# Interfaces_and_Connectors.net
KiCad netlist of a schematic drawn in Altium Designer
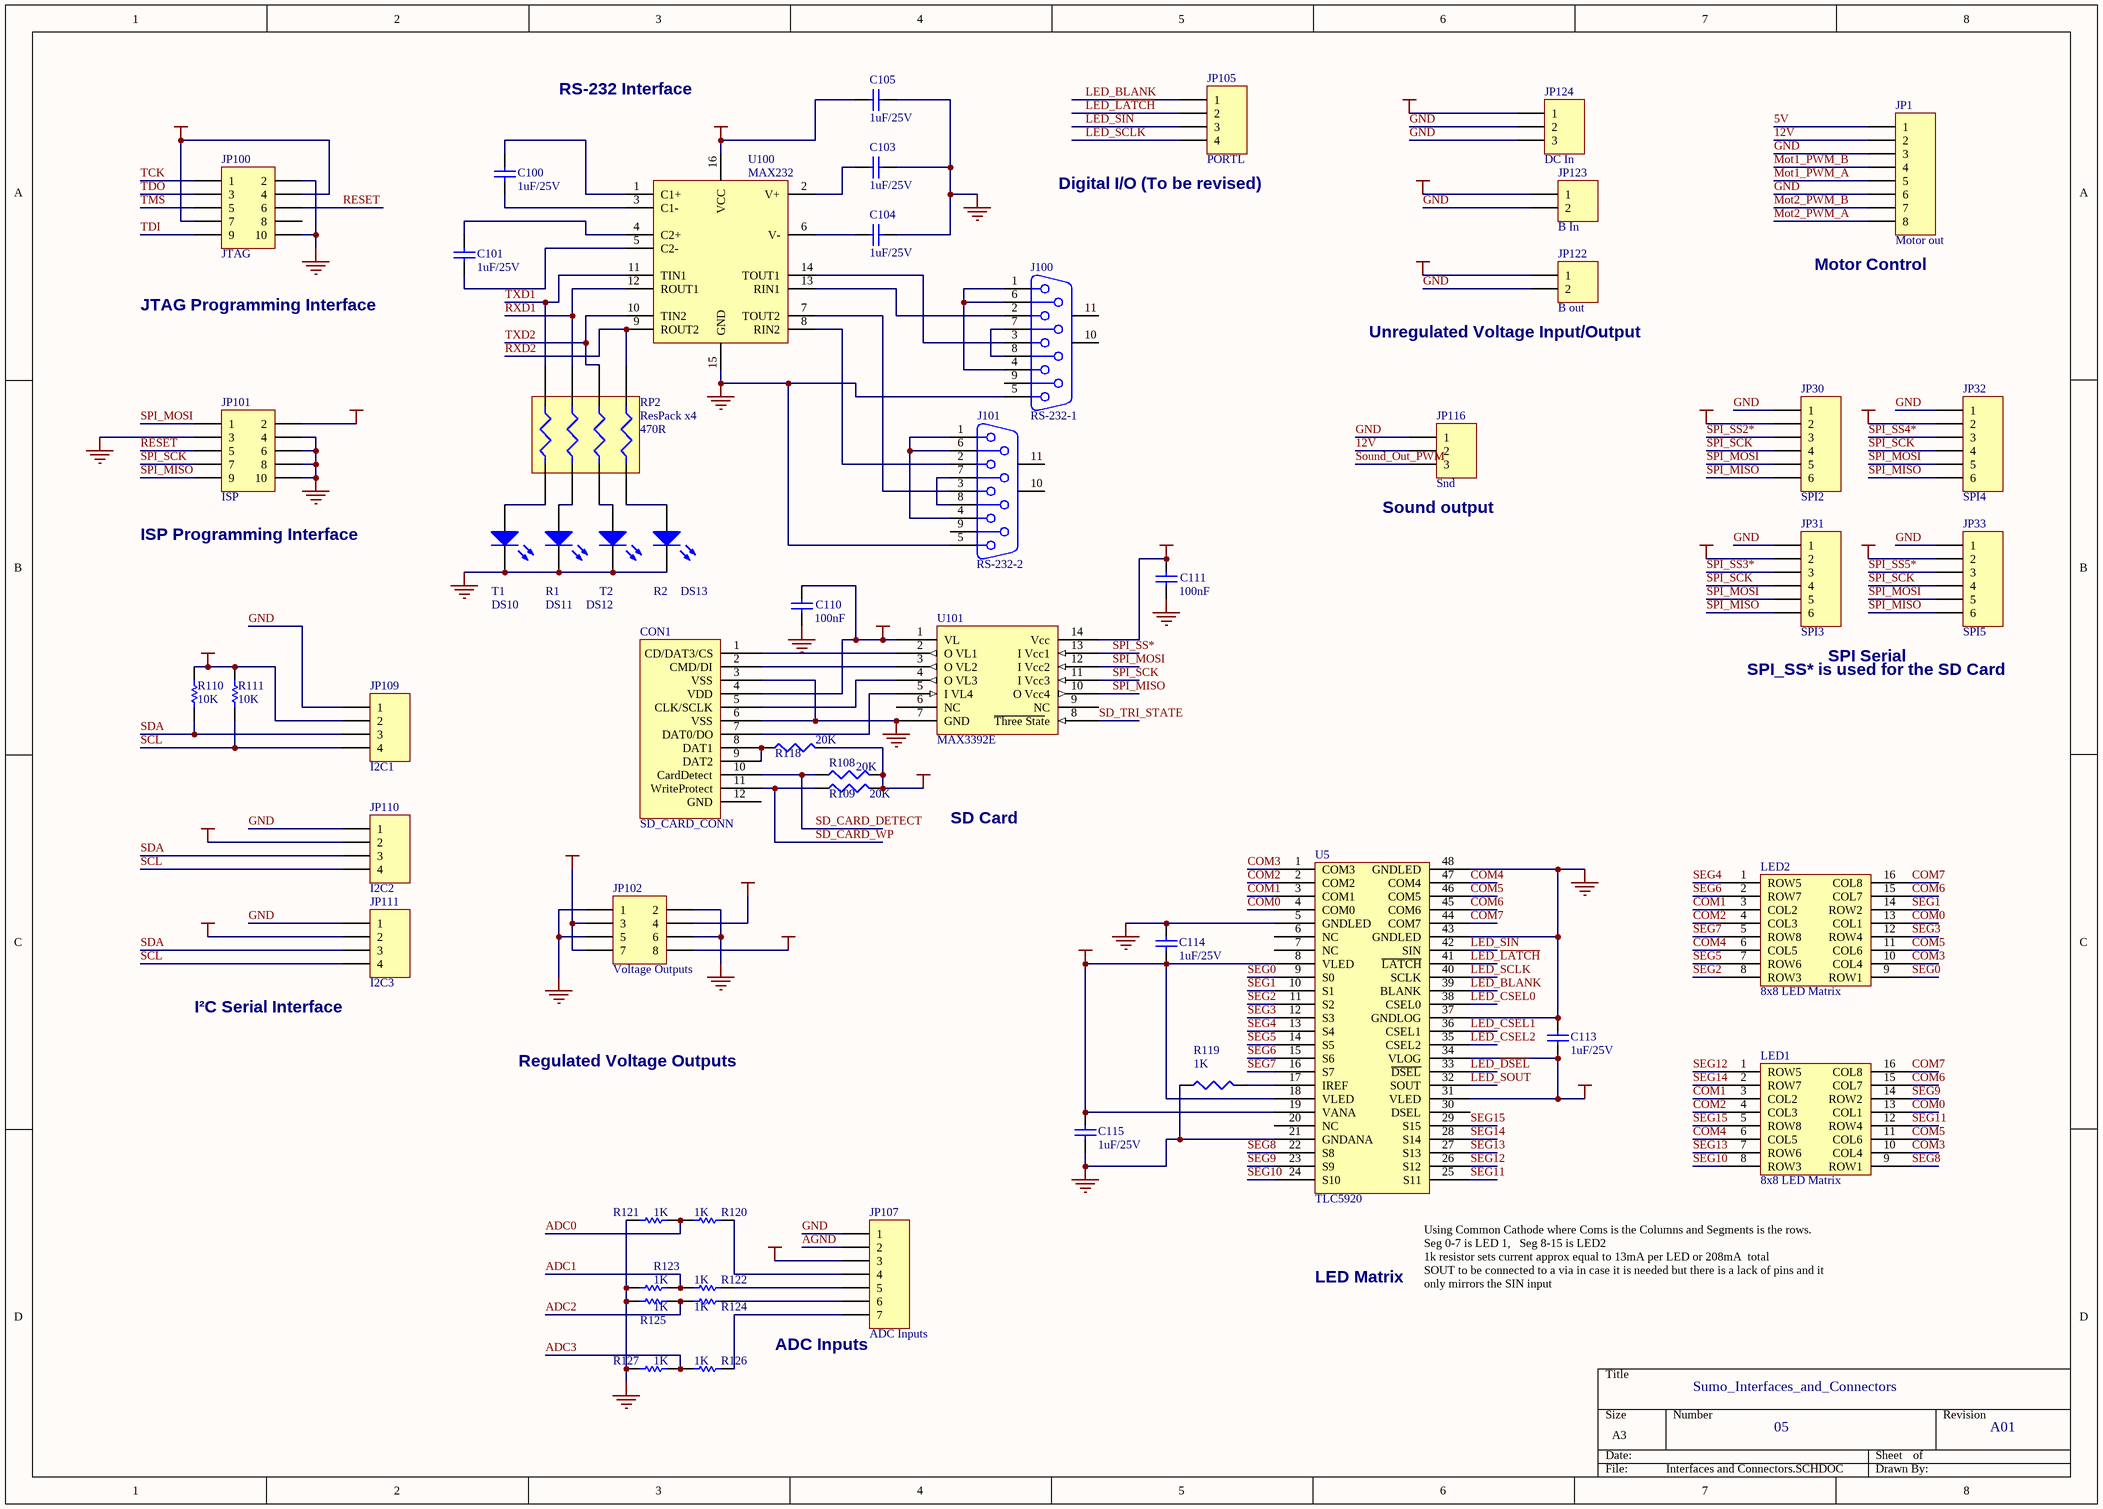
[diagram p0: Interfaces and Connectors.SCHDOC]

(export (version "E")
  (design (tool "Eeschema 10.0.6"))
  (components
    (comp (ref "C100")
      (value "1uF/25V")
      (footprint "CC2012-0805")
      (description "Capacitor (Semiconductor SIM Model)")
      (fields (field (name "Comment") "Cap Semi") (field (name "PUBLISHER") "Altium Limited"))
      (libsource (lib "Miscellaneous Devices") (part "Cap Semi"))
    )
    (comp (ref "C101")
      (value "1uF/25V")
      (footprint "CC2012-0805")
      (description "Capacitor (Semiconductor SIM Model)")
      (fields (field (name "Comment") "Cap Semi") (field (name "PUBLISHER") "Altium Limited"))
      (libsource (lib "Miscellaneous Devices") (part "Cap Semi"))
    )
    (comp (ref "C103")
      (value "1uF/25V")
      (footprint "CC2012-0805")
      (description "Capacitor (Semiconductor SIM Model)")
      (fields (field (name "Comment") "Cap Semi") (field (name "PUBLISHER") "Altium Limited"))
      (libsource (lib "Miscellaneous Devices") (part "Cap Semi"))
    )
    (comp (ref "C104")
      (value "1uF/25V")
      (footprint "CC2012-0805")
      (description "Capacitor (Semiconductor SIM Model)")
      (fields (field (name "Comment") "Cap Semi") (field (name "PUBLISHER") "Altium Limited"))
      (libsource (lib "Miscellaneous Devices") (part "Cap Semi"))
    )
    (comp (ref "C105")
      (value "1uF/25V")
      (footprint "CC2012-0805")
      (description "Capacitor (Semiconductor SIM Model)")
      (fields (field (name "Comment") "Cap Semi") (field (name "PUBLISHER") "Altium Limited"))
      (libsource (lib "Miscellaneous Devices") (part "Cap Semi"))
    )
    (comp (ref "C110")
      (value "100nF")
      (footprint "CC2012-0805")
      (description "Capacitor (Semiconductor SIM Model)")
      (fields (field (name "Comment") "Cap Semi") (field (name "PUBLISHER") "Altium Limited"))
      (libsource (lib "Miscellaneous Devices") (part "Cap Semi"))
    )
    (comp (ref "C111")
      (value "100nF")
      (footprint "CC2012-0805")
      (description "Capacitor (Semiconductor SIM Model)")
      (fields (field (name "Comment") "Cap Semi") (field (name "PUBLISHER") "Altium Limited"))
      (libsource (lib "Miscellaneous Devices") (part "Cap Semi"))
    )
    (comp (ref "C113")
      (value "1uF/25V")
      (footprint "CC2012-0805")
      (description "Capacitor (Semiconductor SIM Model)")
      (fields (field (name "Comment") "Cap Semi") (field (name "PUBLISHER") "Altium Limited"))
      (libsource (lib "Miscellaneous Devices") (part "Cap Semi"))
    )
    (comp (ref "C114")
      (value "1uF/25V")
      (footprint "CC2012-0805")
      (description "Capacitor (Semiconductor SIM Model)")
      (fields (field (name "Comment") "Cap Semi") (field (name "PUBLISHER") "Altium Limited"))
      (libsource (lib "Miscellaneous Devices") (part "Cap Semi"))
    )
    (comp (ref "C115")
      (value "1uF/25V")
      (footprint "CC2012-0805")
      (description "Capacitor (Semiconductor SIM Model)")
      (fields (field (name "Comment") "Cap Semi") (field (name "PUBLISHER") "Altium Limited"))
      (libsource (lib "Miscellaneous Devices") (part "Cap Semi"))
    )
    (comp (ref "CON1")
      (value "SD_CARD_CONN")
      (footprint "SD Card AVX")
      (libsource (lib "Sumo") (part "SD_CARD_CONN"))
    )
    (comp (ref "DS10")
      (value "T1")
      (footprint "SMD _LED")
      (description "Typical BLUE SiC LED")
      (fields (field (name "PUBLISHER") "Altium Limited"))
      (libsource (lib "Miscellaneous Devices") (part "LED3"))
    )
    (comp (ref "DS11")
      (value "R1")
      (footprint "SMD _LED")
      (description "Typical BLUE SiC LED")
      (fields (field (name "PUBLISHER") "Altium Limited"))
      (libsource (lib "Miscellaneous Devices") (part "LED3"))
    )
    (comp (ref "DS12")
      (value "T2")
      (footprint "SMD _LED")
      (description "Typical BLUE SiC LED")
      (fields (field (name "PUBLISHER") "Altium Limited"))
      (libsource (lib "Miscellaneous Devices") (part "LED3"))
    )
    (comp (ref "DS13")
      (value "R2")
      (footprint "SMD _LED")
      (description "Typical BLUE SiC LED")
      (fields (field (name "PUBLISHER") "Altium Limited"))
      (libsource (lib "Miscellaneous Devices") (part "LED3"))
    )
    (comp (ref "J100")
      (value "RS-232-1")
      (footprint "DSUB1.385-2H9 Simple")
      (description "Receptacle Assembly, 9 Position, Right Angle")
      (fields (field (name "PUBLISHER") "Altium Limited"))
      (libsource (lib "Miscellaneous Connectors") (part "D Connector 9"))
    )
    (comp (ref "J101")
      (value "RS-232-2")
      (footprint "DSUB1.385-2H9 Simple")
      (description "Receptacle Assembly, 9 Position, Right Angle")
      (fields (field (name "PUBLISHER") "Altium Limited"))
      (libsource (lib "Miscellaneous Connectors") (part "D Connector 9"))
    )
    (comp (ref "JP1")
      (value "Motor out")
      (footprint "PHR 1x8 2mm")
      (description "Header, 8-Pin")
      (fields (field (name "PUBLISHER") "Altium Limited"))
      (libsource (lib "Miscellaneous Connectors") (part "Header 8"))
    )
    (comp (ref "JP30")
      (value "SPI2")
      (footprint "ZHR 1x6 1.5mm")
      (description "Header, 6-Pin")
      (fields (field (name "PUBLISHER") "Altium Limited"))
      (libsource (lib "Miscellaneous Connectors") (part "Header 6"))
    )
    (comp (ref "JP31")
      (value "SPI3")
      (footprint "ZHR 1x6 1.5mm")
      (description "Header, 6-Pin")
      (fields (field (name "PUBLISHER") "Altium Limited"))
      (libsource (lib "Miscellaneous Connectors") (part "Header 6"))
    )
    (comp (ref "JP32")
      (value "SPI4")
      (footprint "ZHR 1x6 1.5mm")
      (description "Header, 6-Pin")
      (fields (field (name "PUBLISHER") "Altium Limited"))
      (libsource (lib "Miscellaneous Connectors") (part "Header 6"))
    )
    (comp (ref "JP33")
      (value "SPI5")
      (footprint "ZHR 1x6 1.5mm")
      (description "Header, 6-Pin")
      (fields (field (name "PUBLISHER") "Altium Limited"))
      (libsource (lib "Miscellaneous Connectors") (part "Header 6"))
    )
    (comp (ref "JP100")
      (value "JTAG")
      (footprint "HDR2X5")
      (description "Header, 5-Pin, Dual row")
      (fields (field (name "PUBLISHER") "Altium Limited"))
      (libsource (lib "Miscellaneous Connectors") (part "Header 5X2"))
    )
    (comp (ref "JP101")
      (value "ISP")
      (footprint "HDR2X5")
      (description "Header, 5-Pin, Dual row")
      (fields (field (name "PUBLISHER") "Altium Limited"))
      (libsource (lib "Miscellaneous Connectors") (part "Header 5X2"))
    )
    (comp (ref "JP102")
      (value "Voltage Outputs")
      (footprint "microfit 2x4 3mm")
      (description "Header, 4-Pin, Dual row")
      (fields (field (name "PUBLISHER") "Altium Limited"))
      (libsource (lib "Miscellaneous Connectors") (part "Header 4X2"))
    )
    (comp (ref "JP105")
      (value "PORTL")
      (footprint "EHR 1x4 2.5mm")
      (description "Header, 4-Pin")
      (fields (field (name "PUBLISHER") "Altium Limited"))
      (libsource (lib "Miscellaneous Connectors") (part "Header 4"))
    )
    (comp (ref "JP107")
      (value "ADC Inputs")
      (footprint "KK 1x7 2.54mm")
      (description "Header, 7-Pin")
      (fields (field (name "PUBLISHER") "Altium Limited"))
      (libsource (lib "Miscellaneous Connectors") (part "Header 7"))
    )
    (comp (ref "JP109")
      (value "I2C1")
      (footprint "ZHR 1x4 1.5mm")
      (description "Header, 4-Pin")
      (fields (field (name "PUBLISHER") "Altium Limited"))
      (libsource (lib "Miscellaneous Connectors") (part "Header 4"))
    )
    (comp (ref "JP110")
      (value "I2C2")
      (footprint "ZHR 1x4 1.5mm")
      (description "Header, 4-Pin")
      (fields (field (name "PUBLISHER") "Altium Limited"))
      (libsource (lib "Miscellaneous Connectors") (part "Header 4"))
    )
    (comp (ref "JP111")
      (value "I2C3")
      (footprint "ZHR 1x4 1.5mm")
      (description "Header, 4-Pin")
      (fields (field (name "PUBLISHER") "Altium Limited"))
      (libsource (lib "Miscellaneous Connectors") (part "Header 4"))
    )
    (comp (ref "JP116")
      (value "Snd")
      (footprint "KK 1x3 2.54mm")
      (description "Header, 3-Pin")
      (fields (field (name "PUBLISHER") "Altium Limited"))
      (libsource (lib "Miscellaneous Connectors") (part "Header 3"))
    )
    (comp (ref "JP122")
      (value "B out")
      (footprint "Mini-Fit Jnr 2x1 4.2mm")
      (description "Header, 2-Pin")
      (fields (field (name "PUBLISHER") "Altium Limited"))
      (libsource (lib "Miscellaneous Connectors") (part "Header 2"))
    )
    (comp (ref "JP123")
      (value "B In")
      (footprint "Mini-Fit Jnr 2x1 4.2mm")
      (description "Header, 2-Pin")
      (fields (field (name "PUBLISHER") "Altium Limited"))
      (libsource (lib "Miscellaneous Connectors") (part "Header 2"))
    )
    (comp (ref "JP124")
      (value "DC In")
      (footprint "DC Jack 2.1mm")
      (description "Header, 3-Pin")
      (fields (field (name "PUBLISHER") "Altium Limited"))
      (libsource (lib "Miscellaneous Connectors") (part "Header 3"))
    )
    (comp (ref "LED1")
      (value "8x8 LED Matrix")
      (footprint "8x8 LED matrix")
      (libsource (lib "Sumo") (part "8x8 LED Matrix"))
    )
    (comp (ref "LED2")
      (value "8x8 LED Matrix")
      (footprint "8x8 LED matrix")
      (libsource (lib "Sumo") (part "8x8 LED Matrix"))
    )
    (comp (ref "R108")
      (value "20K")
      (footprint "CR2012-0805")
      (description "Resistor")
      (fields (field (name "Comment") "Res3") (field (name "PUBLISHER") "Altium Limited"))
      (libsource (lib "Miscellaneous Devices") (part "Res3"))
    )
    (comp (ref "R109")
      (value "20K")
      (footprint "CR2012-0805")
      (description "Resistor")
      (fields (field (name "Comment") "Res3") (field (name "PUBLISHER") "Altium Limited"))
      (libsource (lib "Miscellaneous Devices") (part "Res3"))
    )
    (comp (ref "R110")
      (value "10K")
      (footprint "CR2012-0805")
      (description "Resistor")
      (fields (field (name "PUBLISHER") "Altium Limited"))
      (libsource (lib "Miscellaneous Devices") (part "Res1"))
    )
    (comp (ref "R111")
      (value "10K")
      (footprint "CR2012-0805")
      (description "Resistor")
      (fields (field (name "PUBLISHER") "Altium Limited"))
      (libsource (lib "Miscellaneous Devices") (part "Res1"))
    )
    (comp (ref "R118")
      (value "20K")
      (footprint "CR2012-0805")
      (description "Resistor")
      (fields (field (name "Comment") "Res3") (field (name "PUBLISHER") "Altium Limited"))
      (libsource (lib "Miscellaneous Devices") (part "Res3"))
    )
    (comp (ref "R119")
      (value "1K")
      (footprint "CR2012-0805")
      (description "Resistor")
      (fields (field (name "Comment") "Res3") (field (name "PUBLISHER") "Altium Limited"))
      (libsource (lib "Miscellaneous Devices") (part "Res3"))
    )
    (comp (ref "R120")
      (value "1K")
      (footprint "CR2012-0805")
      (description "Resistor")
      (fields (field (name "Comment") "Res1") (field (name "PUBLISHER") "Altium Limited"))
      (libsource (lib "Miscellaneous Devices") (part "Res1"))
    )
    (comp (ref "R121")
      (value "1K")
      (footprint "CR2012-0805")
      (description "Resistor")
      (fields (field (name "Comment") "Res1") (field (name "PUBLISHER") "Altium Limited"))
      (libsource (lib "Miscellaneous Devices") (part "Res1"))
    )
    (comp (ref "R122")
      (value "1K")
      (footprint "CR2012-0805")
      (description "Resistor")
      (fields (field (name "Comment") "Res1") (field (name "PUBLISHER") "Altium Limited"))
      (libsource (lib "Miscellaneous Devices") (part "Res1"))
    )
    (comp (ref "R123")
      (value "1K")
      (footprint "CR2012-0805")
      (description "Resistor")
      (fields (field (name "Comment") "Res1") (field (name "PUBLISHER") "Altium Limited"))
      (libsource (lib "Miscellaneous Devices") (part "Res1"))
    )
    (comp (ref "R124")
      (value "1K")
      (footprint "CR2012-0805")
      (description "Resistor")
      (fields (field (name "Comment") "Res1") (field (name "PUBLISHER") "Altium Limited"))
      (libsource (lib "Miscellaneous Devices") (part "Res1"))
    )
    (comp (ref "R125")
      (value "1K")
      (footprint "CR2012-0805")
      (description "Resistor")
      (fields (field (name "Comment") "Res1") (field (name "PUBLISHER") "Altium Limited"))
      (libsource (lib "Miscellaneous Devices") (part "Res1"))
    )
    (comp (ref "R126")
      (value "1K")
      (footprint "CR2012-0805")
      (description "Resistor")
      (fields (field (name "Comment") "Res1") (field (name "PUBLISHER") "Altium Limited"))
      (libsource (lib "Miscellaneous Devices") (part "Res1"))
    )
    (comp (ref "R127")
      (value "1K")
      (footprint "CR2012-0805")
      (description "Resistor")
      (fields (field (name "Comment") "Res1") (field (name "PUBLISHER") "Altium Limited"))
      (libsource (lib "Miscellaneous Devices") (part "Res1"))
    )
    (comp (ref "RP2")
      (value "ResPack x4")
      (footprint "4x0603 Resistor pack")
      (fields (field (name "ALTIUM_VALUE") "470R"))
      (libsource (lib "Sumo") (part "ResPack x4"))
    )
    (comp (ref "U5")
      (value "TLC5920")
      (footprint "SSO-G48")
      (description "TLC5920 16x8 LED Driver")
      (libsource (lib "Sumo") (part "TLC5920 16x8 LED Driver"))
    )
    (comp (ref "U100")
      (value "MAX232")
      (footprint "SO-G16/C5.85")
      (description "Maxim RS-232 Transceiver")
      (libsource (lib "Sumo") (part "MAX232"))
    )
    (comp (ref "U101") (value "MAX3392E") (footprint "TSSOP14") (libsource (lib "Sumo") (part "MAX3392E")))
  )
  (nets
    (net (code "1") (name "/ADC0") (class "Default")
      (node (ref "R120") (pin "1") (pinfunction "1_1") (pintype "passive"))
      (node (ref "R121") (pin "2") (pinfunction "2_2") (pintype "passive"))
    )
    (net (code "2") (name "/ADC1") (class "Default")
      (node (ref "R122") (pin "1") (pinfunction "1_1") (pintype "passive"))
      (node (ref "R123") (pin "2") (pinfunction "2_2") (pintype "passive"))
    )
    (net (code "3") (name "/ADC2") (class "Default")
      (node (ref "R124") (pin "1") (pinfunction "1_1") (pintype "passive"))
      (node (ref "R125") (pin "2") (pinfunction "2_2") (pintype "passive"))
    )
    (net (code "4") (name "/ADC3") (class "Default")
      (node (ref "R126") (pin "1") (pinfunction "1_1") (pintype "passive"))
      (node (ref "R127") (pin "2") (pinfunction "2_2") (pintype "passive"))
    )
    (net (code "5") (name "/COM0") (class "Default")
      (node (ref "LED1") (pin "13") (pinfunction "COL1_13") (pintype "passive"))
      (node (ref "LED2") (pin "13") (pinfunction "COL1_13") (pintype "passive"))
      (node (ref "U5") (pin "4") (pinfunction "COM0_4") (pintype "passive"))
    )
    (net (code "6") (name "/COM1") (class "Default")
      (node (ref "LED1") (pin "3") (pinfunction "COL2_3") (pintype "passive"))
      (node (ref "LED2") (pin "3") (pinfunction "COL2_3") (pintype "passive"))
      (node (ref "U5") (pin "3") (pinfunction "COM1_3") (pintype "passive"))
    )
    (net (code "7") (name "/COM2") (class "Default")
      (node (ref "LED1") (pin "4") (pinfunction "COL3_4") (pintype "passive"))
      (node (ref "LED2") (pin "4") (pinfunction "COL3_4") (pintype "passive"))
      (node (ref "U5") (pin "2") (pinfunction "COM2_2") (pintype "passive"))
    )
    (net (code "8") (name "/COM3") (class "Default")
      (node (ref "LED1") (pin "10") (pinfunction "COL4_10") (pintype "passive"))
      (node (ref "LED2") (pin "10") (pinfunction "COL4_10") (pintype "passive"))
      (node (ref "U5") (pin "1") (pinfunction "COM3_1") (pintype "passive"))
    )
    (net (code "9") (name "/COM4") (class "Default")
      (node (ref "LED1") (pin "6") (pinfunction "COL5_6") (pintype "passive"))
      (node (ref "LED2") (pin "6") (pinfunction "COL5_6") (pintype "passive"))
      (node (ref "U5") (pin "47") (pinfunction "COM4_47") (pintype "passive"))
    )
    (net (code "10") (name "/COM5") (class "Default")
      (node (ref "LED1") (pin "11") (pinfunction "COL6_11") (pintype "passive"))
      (node (ref "LED2") (pin "11") (pinfunction "COL6_11") (pintype "passive"))
      (node (ref "U5") (pin "46") (pinfunction "COM5_46") (pintype "passive"))
    )
    (net (code "11") (name "/COM6") (class "Default")
      (node (ref "LED1") (pin "15") (pinfunction "COL7_15") (pintype "passive"))
      (node (ref "LED2") (pin "15") (pinfunction "COL7_15") (pintype "passive"))
      (node (ref "U5") (pin "45") (pinfunction "COM6_45") (pintype "passive"))
    )
    (net (code "12") (name "/COM7") (class "Default")
      (node (ref "LED1") (pin "16") (pinfunction "COL8_16") (pintype "passive"))
      (node (ref "LED2") (pin "16") (pinfunction "COL8_16") (pintype "passive"))
      (node (ref "U5") (pin "44") (pinfunction "COM7_44") (pintype "passive"))
    )
    (net (code "13") (name "/LED_BLANK") (class "Default")
      (node (ref "JP105") (pin "1") (pinfunction "1_1") (pintype "passive"))
      (node (ref "U5") (pin "39") (pinfunction "BLANK_39") (pintype "passive"))
    )
    (net (code "14") (name "/LED_CSEL0") (class "Default")
      (node (ref "U5") (pin "38") (pinfunction "CSEL0_38") (pintype "passive"))
    )
    (net (code "15") (name "/LED_CSEL1") (class "Default")
      (node (ref "U5") (pin "36") (pinfunction "CSEL1_36") (pintype "passive"))
    )
    (net (code "16") (name "/LED_CSEL2") (class "Default")
      (node (ref "U5") (pin "35") (pinfunction "CSEL2_35") (pintype "passive"))
    )
    (net (code "17") (name "/LED_SCLK") (class "Default")
      (node (ref "JP105") (pin "4") (pinfunction "4_4") (pintype "passive"))
      (node (ref "U5") (pin "40") (pinfunction "SCLK_40") (pintype "passive"))
    )
    (net (code "18") (name "/LED_SIN") (class "Default")
      (node (ref "JP105") (pin "3") (pinfunction "3_3") (pintype "passive"))
      (node (ref "U5") (pin "42") (pinfunction "SIN_42") (pintype "passive"))
    )
    (net (code "19") (name "/LED_SOUT") (class "Default")
      (node (ref "U5") (pin "32") (pinfunction "SOUT_32") (pintype "passive"))
    )
    (net (code "20") (name "/LED_~{DSEL}") (class "Default")
      (node (ref "U5") (pin "33") (pinfunction "~{DSEL}_33") (pintype "passive"))
    )
    (net (code "21") (name "/LED_~{LATCH}") (class "Default")
      (node (ref "JP105") (pin "2") (pinfunction "2_2") (pintype "passive"))
      (node (ref "U5") (pin "41") (pinfunction "~{LATCH}_41") (pintype "passive"))
    )
    (net (code "22") (name "/Mot1_PWM_A") (class "Default")
      (node (ref "JP1") (pin "5") (pinfunction "5_5") (pintype "passive"))
    )
    (net (code "23") (name "/Mot1_PWM_B") (class "Default")
      (node (ref "JP1") (pin "4") (pinfunction "4_4") (pintype "passive"))
    )
    (net (code "24") (name "/Mot2_PWM_A") (class "Default")
      (node (ref "JP1") (pin "8") (pinfunction "8_8") (pintype "passive"))
    )
    (net (code "25") (name "/Mot2_PWM_B") (class "Default")
      (node (ref "JP1") (pin "7") (pinfunction "7_7") (pintype "passive"))
    )
    (net (code "26") (name "/RESET") (class "Default")
      (node (ref "JP100") (pin "6") (pinfunction "6_6") (pintype "passive"))
      (node (ref "JP101") (pin "5") (pinfunction "5_5") (pintype "passive"))
    )
    (net (code "27") (name "/RXD1") (class "Default")
      (node (ref "RP2") (pin "7") (pintype "passive"))
      (node (ref "U100") (pin "12") (pinfunction "ROUT1_12") (pintype "passive"))
    )
    (net (code "28") (name "/RXD2") (class "Default")
      (node (ref "RP2") (pin "5") (pintype "passive"))
      (node (ref "U100") (pin "9") (pinfunction "ROUT2_9") (pintype "passive"))
    )
    (net (code "29") (name "/SCL") (class "Default")
      (node (ref "JP109") (pin "4") (pinfunction "4_4") (pintype "passive"))
      (node (ref "JP110") (pin "4") (pinfunction "4_4") (pintype "passive"))
      (node (ref "JP111") (pin "4") (pinfunction "4_4") (pintype "passive"))
      (node (ref "R111") (pin "1") (pinfunction "1_1") (pintype "passive"))
    )
    (net (code "30") (name "/SDA") (class "Default")
      (node (ref "JP109") (pin "3") (pinfunction "3_3") (pintype "passive"))
      (node (ref "JP110") (pin "3") (pinfunction "3_3") (pintype "passive"))
      (node (ref "JP111") (pin "3") (pinfunction "3_3") (pintype "passive"))
      (node (ref "R110") (pin "1") (pinfunction "1_1") (pintype "passive"))
    )
    (net (code "31") (name "/SD_CARD_DETECT") (class "Default")
      (node (ref "CON1") (pin "10") (pinfunction "CardDetect_10") (pintype "passive"))
      (node (ref "R108") (pin "1") (pinfunction "1_1") (pintype "passive"))
    )
    (net (code "32") (name "/SD_CARD_WP") (class "Default")
      (node (ref "CON1") (pin "11") (pinfunction "WriteProtect_11") (pintype "passive"))
      (node (ref "R109") (pin "1") (pinfunction "1_1") (pintype "passive"))
    )
    (net (code "33") (name "/SD_TRI_STATE") (class "Default")
      (node (ref "U101") (pin "8") (pinfunction "~{Three_Stat}e_8") (pintype "input"))
    )
    (net (code "34") (name "/SEG0") (class "Default")
      (node (ref "LED2") (pin "9") (pinfunction "ROW1_9") (pintype "passive"))
      (node (ref "U5") (pin "9") (pinfunction "S0_9") (pintype "passive"))
    )
    (net (code "35") (name "/SEG1") (class "Default")
      (node (ref "LED2") (pin "14") (pinfunction "ROW2_14") (pintype "passive"))
      (node (ref "U5") (pin "10") (pinfunction "S1_10") (pintype "passive"))
    )
    (net (code "36") (name "/SEG2") (class "Default")
      (node (ref "LED2") (pin "8") (pinfunction "ROW3_8") (pintype "passive"))
      (node (ref "U5") (pin "11") (pinfunction "S2_11") (pintype "passive"))
    )
    (net (code "37") (name "/SEG3") (class "Default")
      (node (ref "LED2") (pin "12") (pinfunction "ROW4_12") (pintype "passive"))
      (node (ref "U5") (pin "12") (pinfunction "S3_12") (pintype "passive"))
    )
    (net (code "38") (name "/SEG4") (class "Default")
      (node (ref "LED2") (pin "1") (pinfunction "ROW5_1") (pintype "passive"))
      (node (ref "U5") (pin "13") (pinfunction "S4_13") (pintype "passive"))
    )
    (net (code "39") (name "/SEG5") (class "Default")
      (node (ref "LED2") (pin "7") (pinfunction "ROW6_7") (pintype "passive"))
      (node (ref "U5") (pin "14") (pinfunction "S5_14") (pintype "passive"))
    )
    (net (code "40") (name "/SEG6") (class "Default")
      (node (ref "LED2") (pin "2") (pinfunction "ROW7_2") (pintype "passive"))
      (node (ref "U5") (pin "15") (pinfunction "S6_15") (pintype "passive"))
    )
    (net (code "41") (name "/SEG7") (class "Default")
      (node (ref "LED2") (pin "5") (pinfunction "ROW8_5") (pintype "passive"))
      (node (ref "U5") (pin "16") (pinfunction "S7_16") (pintype "passive"))
    )
    (net (code "42") (name "/SEG8") (class "Default")
      (node (ref "LED1") (pin "9") (pinfunction "ROW1_9") (pintype "passive"))
      (node (ref "U5") (pin "22") (pinfunction "S8_22") (pintype "passive"))
    )
    (net (code "43") (name "/SEG9") (class "Default")
      (node (ref "LED1") (pin "14") (pinfunction "ROW2_14") (pintype "passive"))
      (node (ref "U5") (pin "23") (pinfunction "S9_23") (pintype "passive"))
    )
    (net (code "44") (name "/SEG10") (class "Default")
      (node (ref "LED1") (pin "8") (pinfunction "ROW3_8") (pintype "passive"))
      (node (ref "U5") (pin "24") (pinfunction "S10_24") (pintype "passive"))
    )
    (net (code "45") (name "/SEG11") (class "Default")
      (node (ref "LED1") (pin "12") (pinfunction "ROW4_12") (pintype "passive"))
      (node (ref "U5") (pin "25") (pinfunction "S11_25") (pintype "passive"))
    )
    (net (code "46") (name "/SEG12") (class "Default")
      (node (ref "LED1") (pin "1") (pinfunction "ROW5_1") (pintype "passive"))
      (node (ref "U5") (pin "26") (pinfunction "S12_26") (pintype "passive"))
    )
    (net (code "47") (name "/SEG13") (class "Default")
      (node (ref "LED1") (pin "7") (pinfunction "ROW6_7") (pintype "passive"))
      (node (ref "U5") (pin "27") (pinfunction "S13_27") (pintype "passive"))
    )
    (net (code "48") (name "/SEG14") (class "Default")
      (node (ref "LED1") (pin "2") (pinfunction "ROW7_2") (pintype "passive"))
      (node (ref "U5") (pin "28") (pinfunction "S14_28") (pintype "passive"))
    )
    (net (code "49") (name "/SEG15") (class "Default")
      (node (ref "LED1") (pin "5") (pinfunction "ROW8_5") (pintype "passive"))
      (node (ref "U5") (pin "29") (pinfunction "S15_29") (pintype "passive"))
    )
    (net (code "50") (name "/SPI_MISO") (class "Default")
      (node (ref "JP101") (pin "9") (pinfunction "9_9") (pintype "passive"))
      (node (ref "JP30") (pin "6") (pinfunction "6_6") (pintype "passive"))
      (node (ref "JP31") (pin "6") (pinfunction "6_6") (pintype "passive"))
      (node (ref "JP32") (pin "6") (pinfunction "6_6") (pintype "passive"))
      (node (ref "JP33") (pin "6") (pinfunction "6_6") (pintype "passive"))
      (node (ref "U101") (pin "10") (pinfunction "O_Vcc4_10") (pintype "output"))
    )
    (net (code "51") (name "/SPI_MOSI") (class "Default")
      (node (ref "JP101") (pin "1") (pinfunction "1_1") (pintype "passive"))
      (node (ref "JP30") (pin "5") (pinfunction "5_5") (pintype "passive"))
      (node (ref "JP31") (pin "5") (pinfunction "5_5") (pintype "passive"))
      (node (ref "JP32") (pin "5") (pinfunction "5_5") (pintype "passive"))
      (node (ref "JP33") (pin "5") (pinfunction "5_5") (pintype "passive"))
      (node (ref "U101") (pin "12") (pinfunction "I_Vcc2_12") (pintype "input"))
    )
    (net (code "52") (name "/SPI_SCK") (class "Default")
      (node (ref "JP101") (pin "7") (pinfunction "7_7") (pintype "passive"))
      (node (ref "JP30") (pin "4") (pinfunction "4_4") (pintype "passive"))
      (node (ref "JP31") (pin "4") (pinfunction "4_4") (pintype "passive"))
      (node (ref "JP32") (pin "4") (pinfunction "4_4") (pintype "passive"))
      (node (ref "JP33") (pin "4") (pinfunction "4_4") (pintype "passive"))
      (node (ref "U101") (pin "11") (pinfunction "I_Vcc3_11") (pintype "input"))
    )
    (net (code "53") (name "/SPI_SS*") (class "Default")
      (node (ref "U101") (pin "13") (pinfunction "I_Vcc1_13") (pintype "input"))
    )
    (net (code "54") (name "/SPI_SS2*") (class "Default")
      (node (ref "JP30") (pin "3") (pinfunction "3_3") (pintype "passive"))
    )
    (net (code "55") (name "/SPI_SS3*") (class "Default")
      (node (ref "JP31") (pin "3") (pinfunction "3_3") (pintype "passive"))
    )
    (net (code "56") (name "/SPI_SS4*") (class "Default")
      (node (ref "JP32") (pin "3") (pinfunction "3_3") (pintype "passive"))
    )
    (net (code "57") (name "/SPI_SS5*") (class "Default")
      (node (ref "JP33") (pin "3") (pinfunction "3_3") (pintype "passive"))
    )
    (net (code "58") (name "/Sound_Out_PWM") (class "Default")
      (node (ref "JP116") (pin "3") (pinfunction "3_3") (pintype "passive"))
    )
    (net (code "59") (name "/TCK") (class "Default")
      (node (ref "JP100") (pin "1") (pinfunction "1_1") (pintype "passive"))
    )
    (net (code "60") (name "/TDI") (class "Default")
      (node (ref "JP100") (pin "9") (pinfunction "9_9") (pintype "passive"))
    )
    (net (code "61") (name "/TDO") (class "Default")
      (node (ref "JP100") (pin "3") (pinfunction "3_3") (pintype "passive"))
    )
    (net (code "62") (name "/TMS") (class "Default")
      (node (ref "JP100") (pin "5") (pinfunction "5_5") (pintype "passive"))
    )
    (net (code "63") (name "/TXD1") (class "Default")
      (node (ref "RP2") (pin "8") (pintype "passive"))
      (node (ref "U100") (pin "11") (pinfunction "TIN1_11") (pintype "passive"))
    )
    (net (code "64") (name "/TXD2") (class "Default")
      (node (ref "RP2") (pin "6") (pintype "passive"))
      (node (ref "U100") (pin "10") (pinfunction "TIN2_10") (pintype "passive"))
    )
    (net (code "65") (name "3V3") (class "Default")
      (node (ref "C110") (pin "2") (pinfunction "2_2") (pintype "passive"))
      (node (ref "CON1") (pin "4") (pinfunction "VDD_4") (pintype "passive"))
      (node (ref "JP102") (pin "4") (pinfunction "4_4") (pintype "passive"))
      (node (ref "U101") (pin "1") (pinfunction "VL_1") (pintype "power_in"))
    )
    (net (code "66") (name "5V") (class "Default")
      (node (ref "C105") (pin "1") (pinfunction "1_1") (pintype "passive"))
      (node (ref "C111") (pin "2") (pinfunction "2_2") (pintype "passive"))
      (node (ref "C113") (pin "1") (pinfunction "1_1") (pintype "passive"))
      (node (ref "C114") (pin "1") (pinfunction "1_1") (pintype "passive"))
      (node (ref "C115") (pin "2") (pinfunction "2_2") (pintype "passive"))
      (node (ref "JP1") (pin "1") (pinfunction "1_1") (pintype "passive"))
      (node (ref "JP100") (pin "4") (pinfunction "4_4") (pintype "passive"))
      (node (ref "JP100") (pin "7") (pinfunction "7_7") (pintype "passive"))
      (node (ref "JP101") (pin "2") (pinfunction "2_2") (pintype "passive"))
      (node (ref "JP102") (pin "8") (pinfunction "8_8") (pintype "passive"))
      (node (ref "JP107") (pin "3") (pinfunction "3_3") (pintype "passive"))
      (node (ref "JP109") (pin "2") (pinfunction "2_2") (pintype "passive"))
      (node (ref "JP110") (pin "2") (pinfunction "2_2") (pintype "passive"))
      (node (ref "JP111") (pin "2") (pinfunction "2_2") (pintype "passive"))
      (node (ref "JP30") (pin "2") (pinfunction "2_2") (pintype "passive"))
      (node (ref "JP31") (pin "2") (pinfunction "2_2") (pintype "passive"))
      (node (ref "JP32") (pin "2") (pinfunction "2_2") (pintype "passive"))
      (node (ref "JP33") (pin "2") (pinfunction "2_2") (pintype "passive"))
      (node (ref "R108") (pin "2") (pinfunction "2_2") (pintype "passive"))
      (node (ref "R109") (pin "2") (pinfunction "2_2") (pintype "passive"))
      (node (ref "R110") (pin "2") (pinfunction "2_2") (pintype "passive"))
      (node (ref "R111") (pin "2") (pinfunction "2_2") (pintype "passive"))
      (node (ref "R118") (pin "2") (pinfunction "2_2") (pintype "passive"))
      (node (ref "U100") (pin "16") (pinfunction "VCC_16") (pintype "passive"))
      (node (ref "U101") (pin "14") (pinfunction "Vcc_14") (pintype "power_in"))
      (node (ref "U5") (pin "18") (pinfunction "VLED_18") (pintype "passive"))
      (node (ref "U5") (pin "19") (pinfunction "VANA_19") (pintype "passive"))
      (node (ref "U5") (pin "31") (pinfunction "VLED_31") (pintype "passive"))
      (node (ref "U5") (pin "34") (pinfunction "VLOG_34") (pintype "passive"))
      (node (ref "U5") (pin "8") (pinfunction "VLED_8") (pintype "passive"))
    )
    (net (code "67") (name "12V") (class "Default")
      (node (ref "JP1") (pin "2") (pinfunction "2_2") (pintype "passive"))
      (node (ref "JP102") (pin "3") (pinfunction "3_3") (pintype "passive"))
      (node (ref "JP102") (pin "7") (pinfunction "7_7") (pintype "passive"))
      (node (ref "JP116") (pin "2") (pinfunction "2_2") (pintype "passive"))
    )
    (net (code "68") (name "AGND") (class "Default")
      (node (ref "JP107") (pin "2") (pinfunction "2_2") (pintype "passive"))
      (node (ref "R121") (pin "1") (pinfunction "1_1") (pintype "passive"))
      (node (ref "R123") (pin "1") (pinfunction "1_1") (pintype "passive"))
      (node (ref "R125") (pin "1") (pinfunction "1_1") (pintype "passive"))
      (node (ref "R127") (pin "1") (pinfunction "1_1") (pintype "passive"))
    )
    (net (code "69") (name "GND") (class "Default")
      (node (ref "C103") (pin "2") (pinfunction "2_2") (pintype "passive"))
      (node (ref "C104") (pin "2") (pinfunction "2_2") (pintype "passive"))
      (node (ref "C105") (pin "2") (pinfunction "2_2") (pintype "passive"))
      (node (ref "C110") (pin "1") (pinfunction "1_1") (pintype "passive"))
      (node (ref "C111") (pin "1") (pinfunction "1_1") (pintype "passive"))
      (node (ref "C113") (pin "2") (pinfunction "2_2") (pintype "passive"))
      (node (ref "C114") (pin "2") (pinfunction "2_2") (pintype "passive"))
      (node (ref "C115") (pin "1") (pinfunction "1_1") (pintype "passive"))
      (node (ref "CON1") (pin "3") (pinfunction "VSS_3") (pintype "passive"))
      (node (ref "CON1") (pin "6") (pinfunction "VSS_6") (pintype "passive"))
      (node (ref "DS10") (pin "2") (pinfunction "K_2") (pintype "passive"))
      (node (ref "DS11") (pin "2") (pinfunction "K_2") (pintype "passive"))
      (node (ref "DS12") (pin "2") (pinfunction "K_2") (pintype "passive"))
      (node (ref "DS13") (pin "2") (pinfunction "K_2") (pintype "passive"))
      (node (ref "J100") (pin "5") (pinfunction "5_5") (pintype "passive"))
      (node (ref "J101") (pin "5") (pinfunction "5_5") (pintype "passive"))
      (node (ref "JP1") (pin "3") (pinfunction "3_3") (pintype "passive"))
      (node (ref "JP1") (pin "6") (pinfunction "6_6") (pintype "passive"))
      (node (ref "JP100") (pin "10") (pinfunction "10_10") (pintype "passive"))
      (node (ref "JP100") (pin "2") (pinfunction "2_2") (pintype "passive"))
      (node (ref "JP101") (pin "10") (pinfunction "10_10") (pintype "passive"))
      (node (ref "JP101") (pin "3") (pinfunction "3_3") (pintype "passive"))
      (node (ref "JP101") (pin "4") (pinfunction "4_4") (pintype "passive"))
      (node (ref "JP101") (pin "6") (pinfunction "6_6") (pintype "passive"))
      (node (ref "JP101") (pin "8") (pinfunction "8_8") (pintype "passive"))
      (node (ref "JP102") (pin "1") (pinfunction "1_1") (pintype "passive"))
      (node (ref "JP102") (pin "2") (pinfunction "2_2") (pintype "passive"))
      (node (ref "JP102") (pin "5") (pinfunction "5_5") (pintype "passive"))
      (node (ref "JP102") (pin "6") (pinfunction "6_6") (pintype "passive"))
      (node (ref "JP107") (pin "1") (pinfunction "1_1") (pintype "passive"))
      (node (ref "JP109") (pin "1") (pinfunction "1_1") (pintype "passive"))
      (node (ref "JP110") (pin "1") (pinfunction "1_1") (pintype "passive"))
      (node (ref "JP111") (pin "1") (pinfunction "1_1") (pintype "passive"))
      (node (ref "JP116") (pin "1") (pinfunction "1_1") (pintype "passive"))
      (node (ref "JP122") (pin "2") (pinfunction "2_2") (pintype "passive"))
      (node (ref "JP123") (pin "2") (pinfunction "2_2") (pintype "passive"))
      (node (ref "JP124") (pin "2") (pinfunction "2_2") (pintype "passive"))
      (node (ref "JP124") (pin "3") (pinfunction "3_3") (pintype "passive"))
      (node (ref "JP30") (pin "1") (pinfunction "1_1") (pintype "passive"))
      (node (ref "JP31") (pin "1") (pinfunction "1_1") (pintype "passive"))
      (node (ref "JP32") (pin "1") (pinfunction "1_1") (pintype "passive"))
      (node (ref "JP33") (pin "1") (pinfunction "1_1") (pintype "passive"))
      (node (ref "R119") (pin "1") (pinfunction "1_1") (pintype "passive"))
      (node (ref "U100") (pin "15") (pinfunction "GND_15") (pintype "passive"))
      (node (ref "U101") (pin "7") (pinfunction "GND_7") (pintype "power_in"))
      (node (ref "U5") (pin "21") (pinfunction "GNDANA_21") (pintype "passive"))
      (node (ref "U5") (pin "37") (pinfunction "GNDLOG_37") (pintype "passive"))
      (node (ref "U5") (pin "43") (pinfunction "GNDLED_43") (pintype "passive"))
      (node (ref "U5") (pin "48") (pinfunction "GNDLED_48") (pintype "passive"))
      (node (ref "U5") (pin "5") (pinfunction "GNDLED_5") (pintype "passive"))
    )
    (net (code "70") (name "Net-(CON1-CD{slash}DAT3{slash}CS)") (class "Default")
      (node (ref "CON1") (pin "1") (pinfunction "CD/DAT3/CS_1") (pintype "passive"))
      (node (ref "U101") (pin "2") (pinfunction "O_VL1_2") (pintype "output"))
    )
    (net (code "71") (name "Net-(CON1-CLK{slash}SCLK)") (class "Default")
      (node (ref "CON1") (pin "5") (pinfunction "CLK/SCLK_5") (pintype "passive"))
      (node (ref "U101") (pin "4") (pinfunction "O_VL3_4") (pintype "output"))
    )
    (net (code "72") (name "Net-(CON1-CMD{slash}DI)") (class "Default")
      (node (ref "CON1") (pin "2") (pinfunction "CMD/DI_2") (pintype "passive"))
      (node (ref "U101") (pin "3") (pinfunction "O_VL2_3") (pintype "output"))
    )
    (net (code "73") (name "Net-(CON1-DAT0{slash}DO)") (class "Default")
      (node (ref "CON1") (pin "7") (pinfunction "DAT0/DO_7") (pintype "passive"))
      (node (ref "U101") (pin "5") (pinfunction "I_VL4_5") (pintype "input"))
    )
    (net (code "74") (name "Net-(CON1-DAT1)") (class "Default")
      (node (ref "CON1") (pin "8") (pinfunction "DAT1_8") (pintype "passive"))
      (node (ref "CON1") (pin "9") (pinfunction "DAT2_9") (pintype "passive"))
      (node (ref "R118") (pin "1") (pinfunction "1_1") (pintype "passive"))
    )
    (net (code "75") (name "Net-(DS10-A)") (class "Default")
      (node (ref "DS10") (pin "1") (pinfunction "A_1") (pintype "passive"))
      (node (ref "RP2") (pin "1") (pintype "passive"))
    )
    (net (code "76") (name "Net-(DS11-A)") (class "Default")
      (node (ref "DS11") (pin "1") (pinfunction "A_1") (pintype "passive"))
      (node (ref "RP2") (pin "2") (pintype "passive"))
    )
    (net (code "77") (name "Net-(DS12-A)") (class "Default")
      (node (ref "DS12") (pin "1") (pinfunction "A_1") (pintype "passive"))
      (node (ref "RP2") (pin "3") (pintype "passive"))
    )
    (net (code "78") (name "Net-(DS13-A)") (class "Default")
      (node (ref "DS13") (pin "1") (pinfunction "A_1") (pintype "passive"))
      (node (ref "RP2") (pin "4") (pintype "passive"))
    )
    (net (code "79") (name "Net-(J100-Pad1)") (class "Default")
      (node (ref "J100") (pin "1") (pinfunction "1_1") (pintype "passive"))
      (node (ref "J100") (pin "4") (pinfunction "4_4") (pintype "passive"))
      (node (ref "J100") (pin "6") (pinfunction "6_6") (pintype "passive"))
    )
    (net (code "80") (name "Net-(J100-Pad7)") (class "Default")
      (node (ref "J100") (pin "7") (pinfunction "7_7") (pintype "passive"))
      (node (ref "J100") (pin "8") (pinfunction "8_8") (pintype "passive"))
    )
    (net (code "81") (name "Net-(J101-Pad1)") (class "Default")
      (node (ref "J101") (pin "1") (pinfunction "1_1") (pintype "passive"))
      (node (ref "J101") (pin "4") (pinfunction "4_4") (pintype "passive"))
      (node (ref "J101") (pin "6") (pinfunction "6_6") (pintype "passive"))
    )
    (net (code "82") (name "Net-(J101-Pad7)") (class "Default")
      (node (ref "J101") (pin "7") (pinfunction "7_7") (pintype "passive"))
      (node (ref "J101") (pin "8") (pinfunction "8_8") (pintype "passive"))
    )
    (net (code "83") (name "Net-(JP107-Pad4)") (class "Default")
      (node (ref "JP107") (pin "4") (pinfunction "4_4") (pintype "passive"))
      (node (ref "R120") (pin "2") (pinfunction "2_2") (pintype "passive"))
    )
    (net (code "84") (name "Net-(JP107-Pad5)") (class "Default")
      (node (ref "JP107") (pin "5") (pinfunction "5_5") (pintype "passive"))
      (node (ref "R122") (pin "2") (pinfunction "2_2") (pintype "passive"))
    )
    (net (code "85") (name "Net-(JP107-Pad6)") (class "Default")
      (node (ref "JP107") (pin "6") (pinfunction "6_6") (pintype "passive"))
      (node (ref "R124") (pin "2") (pinfunction "2_2") (pintype "passive"))
    )
    (net (code "86") (name "Net-(JP107-Pad7)") (class "Default")
      (node (ref "JP107") (pin "7") (pinfunction "7_7") (pintype "passive"))
      (node (ref "R126") (pin "2") (pinfunction "2_2") (pintype "passive"))
    )
    (net (code "87") (name "Net-(U5-IREF)") (class "Default")
      (node (ref "R119") (pin "2") (pinfunction "2_2") (pintype "passive"))
      (node (ref "U5") (pin "17") (pinfunction "IREF_17") (pintype "passive"))
    )
    (net (code "88") (name "Net-(U100-C1+)") (class "Default")
      (node (ref "C100") (pin "2") (pinfunction "2_2") (pintype "passive"))
      (node (ref "U100") (pin "1") (pinfunction "C1+_1") (pintype "passive"))
    )
    (net (code "89") (name "Net-(U100-C1-)") (class "Default")
      (node (ref "C100") (pin "1") (pinfunction "1_1") (pintype "passive"))
      (node (ref "U100") (pin "3") (pinfunction "C1-_3") (pintype "passive"))
    )
    (net (code "90") (name "Net-(U100-C2+)") (class "Default")
      (node (ref "C101") (pin "2") (pinfunction "2_2") (pintype "passive"))
      (node (ref "U100") (pin "4") (pinfunction "C2+_4") (pintype "passive"))
    )
    (net (code "91") (name "Net-(U100-C2-)") (class "Default")
      (node (ref "C101") (pin "1") (pinfunction "1_1") (pintype "passive"))
      (node (ref "U100") (pin "5") (pinfunction "C2-_5") (pintype "passive"))
    )
    (net (code "92") (name "Net-(U100-RIN1)") (class "Default")
      (node (ref "J100") (pin "2") (pinfunction "2_2") (pintype "passive"))
      (node (ref "U100") (pin "13") (pinfunction "RIN1_13") (pintype "passive"))
    )
    (net (code "93") (name "Net-(U100-RIN2)") (class "Default")
      (node (ref "J101") (pin "2") (pinfunction "2_2") (pintype "passive"))
      (node (ref "U100") (pin "8") (pinfunction "RIN2_8") (pintype "passive"))
    )
    (net (code "94") (name "Net-(U100-TOUT1)") (class "Default")
      (node (ref "J100") (pin "3") (pinfunction "3_3") (pintype "passive"))
      (node (ref "U100") (pin "14") (pinfunction "TOUT1_14") (pintype "passive"))
    )
    (net (code "95") (name "Net-(U100-TOUT2)") (class "Default")
      (node (ref "J101") (pin "3") (pinfunction "3_3") (pintype "passive"))
      (node (ref "U100") (pin "7") (pinfunction "TOUT2_7") (pintype "passive"))
    )
    (net (code "96") (name "Net-(U100-V+)") (class "Default")
      (node (ref "C103") (pin "1") (pinfunction "1_1") (pintype "passive"))
      (node (ref "U100") (pin "2") (pinfunction "V+_2") (pintype "passive"))
    )
    (net (code "97") (name "Net-(U100-V-)") (class "Default")
      (node (ref "C104") (pin "1") (pinfunction "1_1") (pintype "passive"))
      (node (ref "U100") (pin "6") (pinfunction "V-_6") (pintype "passive"))
    )
    (net (code "98") (name "VBat") (class "Default")
      (node (ref "JP122") (pin "1") (pinfunction "1_1") (pintype "passive"))
    )
    (net (code "99") (name "VBatIn") (class "Default")
      (node (ref "JP123") (pin "1") (pinfunction "1_1") (pintype "passive"))
      (node (ref "JP124") (pin "1") (pinfunction "1_1") (pintype "passive"))
    )
    (net (code "100") (name "unconnected-(CON1-GND-Pad12)") (class "Default")
      (node (ref "CON1") (pin "12") (pinfunction "GND_12") (pintype "passive"))
    )
    (net (code "101") (name "unconnected-(J100-MH1-Pad10)") (class "Default")
      (node (ref "J100") (pin "10") (pinfunction "MH1_10") (pintype "passive"))
    )
    (net (code "102") (name "unconnected-(J100-MH2-Pad11)") (class "Default")
      (node (ref "J100") (pin "11") (pinfunction "MH2_11") (pintype "passive"))
    )
    (net (code "103") (name "unconnected-(J100-Pad9)") (class "Default")
      (node (ref "J100") (pin "9") (pinfunction "9_9") (pintype "passive"))
    )
    (net (code "104") (name "unconnected-(J101-MH1-Pad10)") (class "Default")
      (node (ref "J101") (pin "10") (pinfunction "MH1_10") (pintype "passive"))
    )
    (net (code "105") (name "unconnected-(J101-MH2-Pad11)") (class "Default")
      (node (ref "J101") (pin "11") (pinfunction "MH2_11") (pintype "passive"))
    )
    (net (code "106") (name "unconnected-(J101-Pad9)") (class "Default")
      (node (ref "J101") (pin "9") (pinfunction "9_9") (pintype "passive"))
    )
    (net (code "107") (name "unconnected-(JP100-Pad8)") (class "Default")
      (node (ref "JP100") (pin "8") (pinfunction "8_8") (pintype "passive"))
    )
    (net (code "108") (name "unconnected-(U5-DSEL-Pad30)") (class "Default")
      (node (ref "U5") (pin "30") (pinfunction "DSEL_30") (pintype "passive"))
    )
    (net (code "109") (name "unconnected-(U5-NC-Pad6)") (class "Default")
      (node (ref "U5") (pin "6") (pinfunction "NC_6") (pintype "passive"))
    )
    (net (code "110") (name "unconnected-(U5-NC-Pad7)") (class "Default")
      (node (ref "U5") (pin "7") (pinfunction "NC_7") (pintype "passive"))
    )
    (net (code "111") (name "unconnected-(U5-NC-Pad20)") (class "Default")
      (node (ref "U5") (pin "20") (pinfunction "NC_20") (pintype "passive"))
    )
    (net (code "112") (name "unconnected-(U101-NC-Pad6)") (class "Default")
      (node (ref "U101") (pin "6") (pinfunction "NC_6") (pintype "passive"))
    )
    (net (code "113") (name "unconnected-(U101-NC-Pad9)") (class "Default")
      (node (ref "U101") (pin "9") (pinfunction "NC_9") (pintype "passive"))
    )
  )
)
